# pic_pico.net
KiCad netlist of a schematic drawn in EAGLE
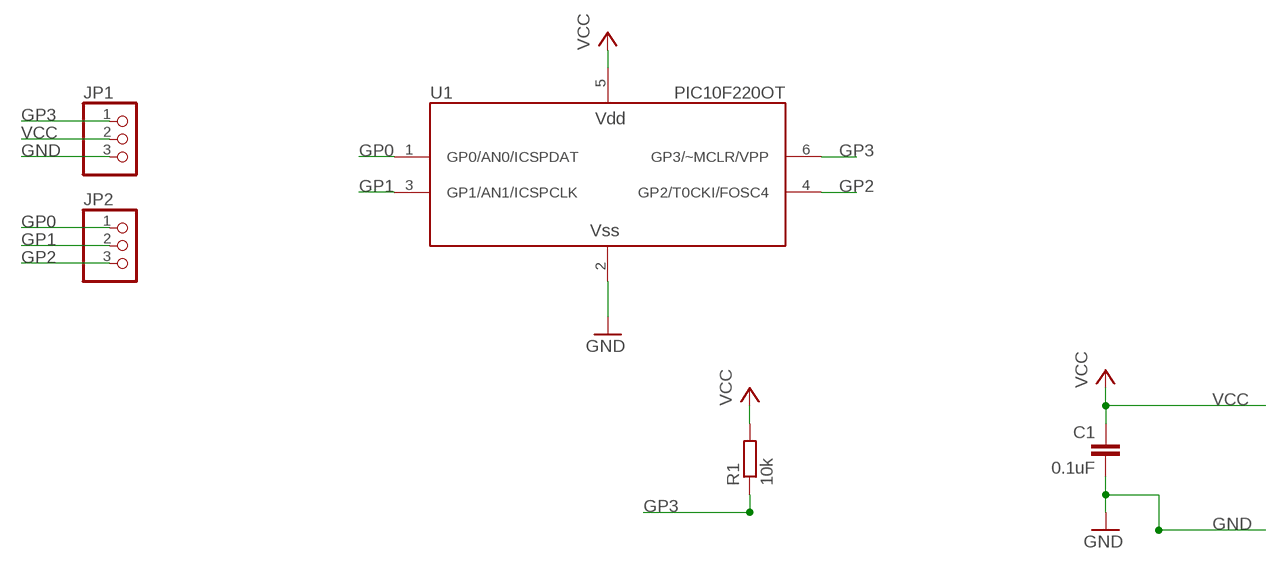
[diagram p0: schematic, sheet 1]

(export (version "E")
  (design (tool "Eeschema 10.0.6"))
  (components
    (comp (ref "C1")
      (value "0.1uF")
      (footprint "eagle-import:C0603")
      (libsource (lib "eagle-import") (part "C-EUC0603"))
    )
    (comp (ref "JP1")
      (value "PINHD-1X3")
      (footprint "eagle-import:1X03")
      (libsource (lib "eagle-import") (part "PINHD-1X3"))
    )
    (comp (ref "JP2")
      (value "PINHD-1X3")
      (footprint "eagle-import:1X03")
      (libsource (lib "eagle-import") (part "PINHD-1X3"))
    )
    (comp (ref "R1")
      (value "10k")
      (footprint "eagle-import:R0603")
      (libsource (lib "eagle-import") (part "R-EU_R0603"))
    )
    (comp (ref "U1")
      (value "PIC10F220OT")
      (footprint "eagle-import:SOT-23-6")
      (libsource (lib "eagle-import") (part "PIC10F22OT0"))
    )
  )
  (nets
    (net (code "1") (name "/GP0") (class "Default")
      (node (ref "JP2") (pin "1") (pinfunction "1_1") (pintype "passive"))
      (node (ref "U1") (pin "1") (pinfunction "GP0/AN0/ICSPDAT_1") (pintype "bidirectional"))
    )
    (net (code "2") (name "/GP1") (class "Default")
      (node (ref "JP2") (pin "2") (pinfunction "2_2") (pintype "passive"))
      (node (ref "U1") (pin "3") (pinfunction "GP1/AN1/ICSPCLK_3") (pintype "bidirectional"))
    )
    (net (code "3") (name "/GP2") (class "Default")
      (node (ref "JP2") (pin "3") (pinfunction "3_3") (pintype "passive"))
      (node (ref "U1") (pin "4") (pinfunction "GP2/T0CKI/FOSC4_4") (pintype "bidirectional"))
    )
    (net (code "4") (name "/GP3") (class "Default")
      (node (ref "JP1") (pin "1") (pinfunction "1_1") (pintype "passive"))
      (node (ref "R1") (pin "1") (pinfunction "1_1") (pintype "passive"))
      (node (ref "U1") (pin "6") (pinfunction "GP3/~{MCLR/VPP}_6") (pintype "input"))
    )
    (net (code "5") (name "GND") (class "Default")
      (node (ref "C1") (pin "2") (pinfunction "2_2") (pintype "passive"))
      (node (ref "JP1") (pin "3") (pinfunction "3_3") (pintype "passive"))
      (node (ref "U1") (pin "2") (pinfunction "VSS_2") (pintype "power_in"))
    )
    (net (code "6") (name "VCC") (class "Default")
      (node (ref "C1") (pin "1") (pinfunction "1_1") (pintype "passive"))
      (node (ref "JP1") (pin "2") (pinfunction "2_2") (pintype "passive"))
      (node (ref "R1") (pin "2") (pinfunction "2_2") (pintype "passive"))
      (node (ref "U1") (pin "5") (pinfunction "VDD_5") (pintype "power_in"))
    )
  )
)
